# dht11.net
KiCad netlist of a schematic drawn in EAGLE
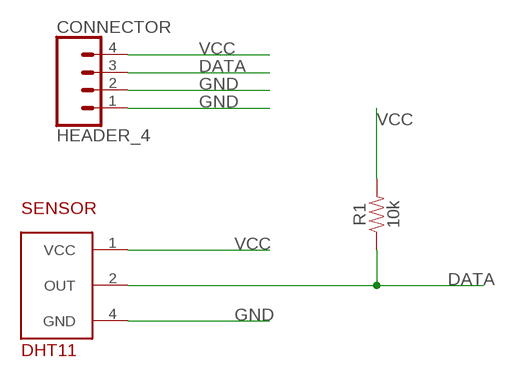
[diagram p0: schematic, sheet 1]

(export (version "E")
  (design (tool "Eeschema 10.0.6"))
  (components
    (comp (ref "CONNECTOR")
      (value "HEADER_4")
      (footprint "eagle-import:MOLEX-1X4")
      (libsource (lib "eagle-import") (part "CONN_04POLAR"))
    )
    (comp (ref "R1")
      (value "10k")
      (footprint "eagle-import:AXIAL-0.3")
      (libsource (lib "eagle-import") (part "10KOHM-HORIZ-1/4W-1%"))
    )
    (comp (ref "SENSOR")
      (value "DHT11")
      (footprint "eagle-import:DHT11")
      (libsource (lib "eagle-import") (part "DHT11"))
    )
  )
  (nets
    (net (code "1") (name "/DATA") (class "Default")
      (node (ref "CONNECTOR") (pin "3") (pinfunction "3_3") (pintype "passive"))
      (node (ref "R1") (pin "P$1") (pinfunction "1_P$1") (pintype "passive"))
      (node (ref "SENSOR") (pin "2") (pinfunction "OUT_2") (pintype "bidirectional"))
    )
    (net (code "2") (name "/GND") (class "Default")
      (node (ref "CONNECTOR") (pin "1") (pinfunction "1_1") (pintype "passive"))
      (node (ref "CONNECTOR") (pin "2") (pinfunction "2_2") (pintype "passive"))
      (node (ref "SENSOR") (pin "4") (pinfunction "GND_4") (pintype "power_in"))
    )
    (net (code "3") (name "/VCC") (class "Default")
      (node (ref "CONNECTOR") (pin "4") (pinfunction "4_4") (pintype "passive"))
      (node (ref "R1") (pin "P$2") (pinfunction "2_P$2") (pintype "passive"))
      (node (ref "SENSOR") (pin "1") (pinfunction "VCC_1") (pintype "power_in"))
    )
  )
)
